# FPGA_GPIO_Part1.net
KiCad netlist of a schematic drawn in Altium Designer
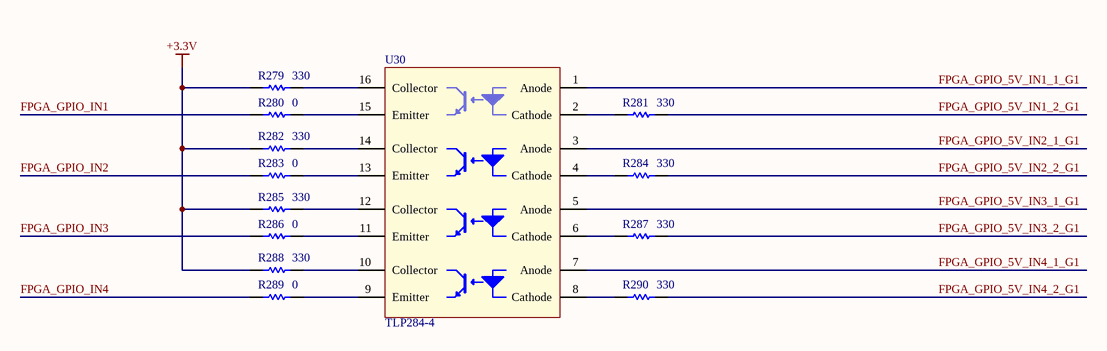
[diagram p0: FPGA_GPIO_Part1.SchDoc]

(export (version "E")
  (design (tool "Eeschema 10.0.6"))
  (components
    (comp (ref "R279")
      (value "330")
      (footprint "1608[0603]")
      (description "Resistor")
      (fields (field (name "Comment") "Res1") (field (name "PUBLISHER") "Altium Limited"))
      (libsource (lib "Miscellaneous Devices") (part "Res1"))
    )
    (comp (ref "R280")
      (value "0")
      (footprint "1608[0603]")
      (description "Resistor")
      (fields (field (name "Comment") "Res1") (field (name "PUBLISHER") "Altium Limited"))
      (libsource (lib "Miscellaneous Devices") (part "Res1"))
    )
    (comp (ref "R281")
      (value "330")
      (footprint "1608[0603]")
      (description "Resistor")
      (fields (field (name "Comment") "Res1") (field (name "PUBLISHER") "Altium Limited"))
      (libsource (lib "Miscellaneous Devices") (part "Res1"))
    )
    (comp (ref "R282")
      (value "330")
      (footprint "1608[0603]")
      (description "Resistor")
      (fields (field (name "Comment") "Res1") (field (name "PUBLISHER") "Altium Limited"))
      (libsource (lib "Miscellaneous Devices") (part "Res1"))
    )
    (comp (ref "R283")
      (value "0")
      (footprint "1608[0603]")
      (description "Resistor")
      (fields (field (name "Comment") "Res1") (field (name "PUBLISHER") "Altium Limited"))
      (libsource (lib "Miscellaneous Devices") (part "Res1"))
    )
    (comp (ref "R284")
      (value "330")
      (footprint "1608[0603]")
      (description "Resistor")
      (fields (field (name "Comment") "Res1") (field (name "PUBLISHER") "Altium Limited"))
      (libsource (lib "Miscellaneous Devices") (part "Res1"))
    )
    (comp (ref "R285")
      (value "330")
      (footprint "1608[0603]")
      (description "Resistor")
      (fields (field (name "Comment") "Res1") (field (name "PUBLISHER") "Altium Limited"))
      (libsource (lib "Miscellaneous Devices") (part "Res1"))
    )
    (comp (ref "R286")
      (value "0")
      (footprint "1608[0603]")
      (description "Resistor")
      (fields (field (name "Comment") "Res1") (field (name "PUBLISHER") "Altium Limited"))
      (libsource (lib "Miscellaneous Devices") (part "Res1"))
    )
    (comp (ref "R287")
      (value "330")
      (footprint "1608[0603]")
      (description "Resistor")
      (fields (field (name "Comment") "Res1") (field (name "PUBLISHER") "Altium Limited"))
      (libsource (lib "Miscellaneous Devices") (part "Res1"))
    )
    (comp (ref "R288")
      (value "330")
      (footprint "1608[0603]")
      (description "Resistor")
      (fields (field (name "Comment") "Res1") (field (name "PUBLISHER") "Altium Limited"))
      (libsource (lib "Miscellaneous Devices") (part "Res1"))
    )
    (comp (ref "R289")
      (value "0")
      (footprint "1608[0603]")
      (description "Resistor")
      (fields (field (name "Comment") "Res1") (field (name "PUBLISHER") "Altium Limited"))
      (libsource (lib "Miscellaneous Devices") (part "Res1"))
    )
    (comp (ref "R290")
      (value "330")
      (footprint "1608[0603]")
      (description "Resistor")
      (fields (field (name "Comment") "Res1") (field (name "PUBLISHER") "Altium Limited"))
      (libsource (lib "Miscellaneous Devices") (part "Res1"))
    )
    (comp (ref "U30")
      (value "TLP284-4")
      (footprint "TLP284-4")
      (libsource (lib "DSP_FPGA") (part "TLP284-4"))
    )
  )
  (nets
    (net (code "1") (name "+3.3V") (class "Default")
      (node (ref "R279") (pin "1") (pinfunction "1_1") (pintype "passive"))
      (node (ref "R282") (pin "1") (pinfunction "1_1") (pintype "passive"))
      (node (ref "R285") (pin "1") (pinfunction "1_1") (pintype "passive"))
      (node (ref "R288") (pin "1") (pinfunction "1_1") (pintype "passive"))
    )
    (net (code "2") (name "/FPGA_GPIO_5V_IN1_1_G1") (class "Default")
      (node (ref "U30") (pin "1") (pinfunction "Anode_1") (pintype "passive"))
    )
    (net (code "3") (name "/FPGA_GPIO_5V_IN1_2_G1") (class "Default")
      (node (ref "R281") (pin "2") (pinfunction "2_2") (pintype "passive"))
    )
    (net (code "4") (name "/FPGA_GPIO_5V_IN2_1_G1") (class "Default")
      (node (ref "U30") (pin "3") (pinfunction "Anode_3") (pintype "passive"))
    )
    (net (code "5") (name "/FPGA_GPIO_5V_IN2_2_G1") (class "Default")
      (node (ref "R284") (pin "2") (pinfunction "2_2") (pintype "passive"))
    )
    (net (code "6") (name "/FPGA_GPIO_5V_IN3_1_G1") (class "Default")
      (node (ref "U30") (pin "5") (pinfunction "Anode_5") (pintype "passive"))
    )
    (net (code "7") (name "/FPGA_GPIO_5V_IN3_2_G1") (class "Default")
      (node (ref "R287") (pin "2") (pinfunction "2_2") (pintype "passive"))
    )
    (net (code "8") (name "/FPGA_GPIO_5V_IN4_1_G1") (class "Default")
      (node (ref "U30") (pin "7") (pinfunction "Anode_7") (pintype "passive"))
    )
    (net (code "9") (name "/FPGA_GPIO_5V_IN4_2_G1") (class "Default")
      (node (ref "R290") (pin "2") (pinfunction "2_2") (pintype "passive"))
    )
    (net (code "10") (name "/FPGA_GPIO_IN1") (class "Default")
      (node (ref "R280") (pin "1") (pinfunction "1_1") (pintype "passive"))
    )
    (net (code "11") (name "/FPGA_GPIO_IN2") (class "Default")
      (node (ref "R283") (pin "1") (pinfunction "1_1") (pintype "passive"))
    )
    (net (code "12") (name "/FPGA_GPIO_IN3") (class "Default")
      (node (ref "R286") (pin "1") (pinfunction "1_1") (pintype "passive"))
    )
    (net (code "13") (name "/FPGA_GPIO_IN4") (class "Default")
      (node (ref "R289") (pin "1") (pinfunction "1_1") (pintype "passive"))
    )
    (net (code "14") (name "Net-(R279-Pad2)") (class "Default")
      (node (ref "R279") (pin "2") (pinfunction "2_2") (pintype "passive"))
      (node (ref "U30") (pin "16") (pinfunction "Collector_16") (pintype "passive"))
    )
    (net (code "15") (name "Net-(R280-Pad2)") (class "Default")
      (node (ref "R280") (pin "2") (pinfunction "2_2") (pintype "passive"))
      (node (ref "U30") (pin "15") (pinfunction "Emitter_15") (pintype "passive"))
    )
    (net (code "16") (name "Net-(R281-Pad1)") (class "Default")
      (node (ref "R281") (pin "1") (pinfunction "1_1") (pintype "passive"))
      (node (ref "U30") (pin "2") (pinfunction "Cathode_2") (pintype "passive"))
    )
    (net (code "17") (name "Net-(R282-Pad2)") (class "Default")
      (node (ref "R282") (pin "2") (pinfunction "2_2") (pintype "passive"))
      (node (ref "U30") (pin "14") (pinfunction "Collector_14") (pintype "passive"))
    )
    (net (code "18") (name "Net-(R283-Pad2)") (class "Default")
      (node (ref "R283") (pin "2") (pinfunction "2_2") (pintype "passive"))
      (node (ref "U30") (pin "13") (pinfunction "Emitter_13") (pintype "passive"))
    )
    (net (code "19") (name "Net-(R284-Pad1)") (class "Default")
      (node (ref "R284") (pin "1") (pinfunction "1_1") (pintype "passive"))
      (node (ref "U30") (pin "4") (pinfunction "Cathode_4") (pintype "passive"))
    )
    (net (code "20") (name "Net-(R285-Pad2)") (class "Default")
      (node (ref "R285") (pin "2") (pinfunction "2_2") (pintype "passive"))
      (node (ref "U30") (pin "12") (pinfunction "Collector_12") (pintype "passive"))
    )
    (net (code "21") (name "Net-(R286-Pad2)") (class "Default")
      (node (ref "R286") (pin "2") (pinfunction "2_2") (pintype "passive"))
      (node (ref "U30") (pin "11") (pinfunction "Emitter_11") (pintype "passive"))
    )
    (net (code "22") (name "Net-(R287-Pad1)") (class "Default")
      (node (ref "R287") (pin "1") (pinfunction "1_1") (pintype "passive"))
      (node (ref "U30") (pin "6") (pinfunction "Cathode_6") (pintype "passive"))
    )
    (net (code "23") (name "Net-(R288-Pad2)") (class "Default")
      (node (ref "R288") (pin "2") (pinfunction "2_2") (pintype "passive"))
      (node (ref "U30") (pin "10") (pinfunction "Collector_10") (pintype "passive"))
    )
    (net (code "24") (name "Net-(R289-Pad2)") (class "Default")
      (node (ref "R289") (pin "2") (pinfunction "2_2") (pintype "passive"))
      (node (ref "U30") (pin "9") (pinfunction "Emitter_9") (pintype "passive"))
    )
    (net (code "25") (name "Net-(R290-Pad1)") (class "Default")
      (node (ref "R290") (pin "1") (pinfunction "1_1") (pintype "passive"))
      (node (ref "U30") (pin "8") (pinfunction "Cathode_8") (pintype "passive"))
    )
  )
)
